# IB_V2_POWER.net
KiCad netlist of a schematic drawn in Altium Designer
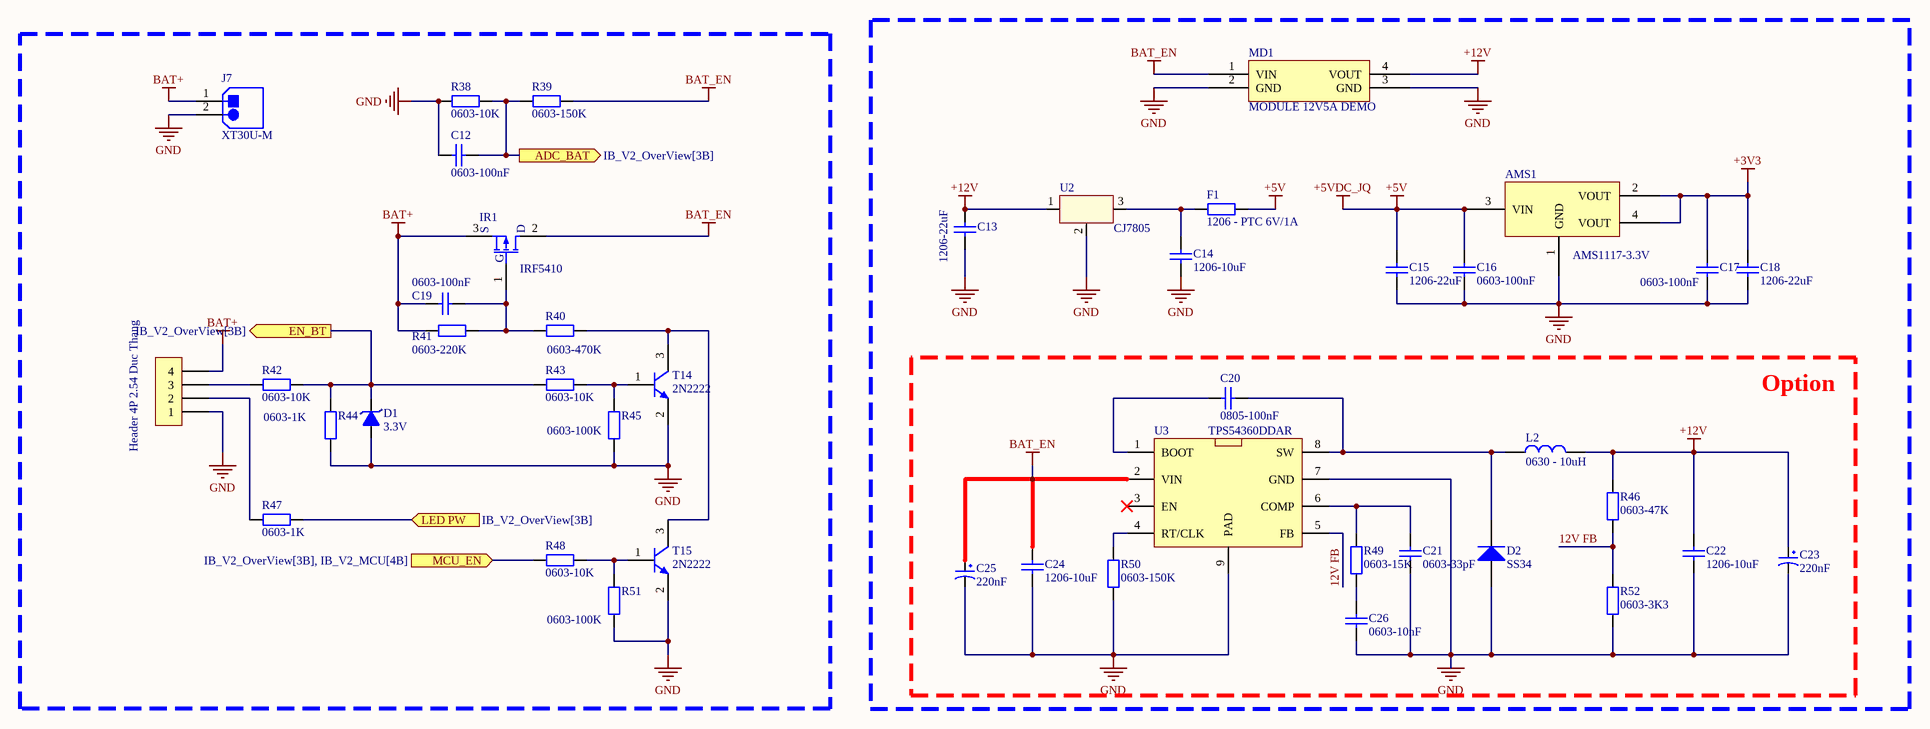
[diagram p0: IB_V2_POWER.SchDoc]

(export (version "E")
  (design (tool "Eeschema 10.0.6"))
  (components
    (comp (ref "AMS1")
      (value "AMS1117-3.3V")
      (footprint "SOT223")
      (description "Dán")
      (libsource (lib "TBS19_MineFiled_V4") (part "AMS1117 SMD"))
    )
    (comp (ref "C12")
      (value "0603-100nF")
      (footprint "Cap 0603")
      (description "50V 100nF X7R ±5% 0603 Multilayer Ceramic Capacitors MLCC - SMD/SMT ROHS")
      (libsource (lib "thuvien_cty") (part "Cap 0603 100nF"))
    )
    (comp (ref "C13")
      (value "1206-22uF")
      (footprint "Cap 1206")
      (description "25V 22uF X5R ±10% 1206 Multilayer Ceramic Capacitors MLCC - SMD/SMT ROHS")
      (libsource (lib "thuvien_cty") (part "Cap 1206 22uF"))
    )
    (comp (ref "C14")
      (value "1206-10uF")
      (footprint "Cap 1206")
      (description "50V 10uF X5R ±10% 1206 Multilayer Ceramic Capacitors MLCC - SMD/SMT ROHS")
      (libsource (lib "thuvien_cty") (part "Cap 1206 10uF"))
    )
    (comp (ref "C15")
      (value "1206-22uF")
      (footprint "Cap 1206")
      (description "25V 22uF X5R ±10% 1206 Multilayer Ceramic Capacitors MLCC - SMD/SMT ROHS")
      (libsource (lib "thuvien_cty") (part "Cap 1206 22uF"))
    )
    (comp (ref "C16")
      (value "0603-100nF")
      (footprint "Cap 0603")
      (description "50V 100nF X7R ±5% 0603 Multilayer Ceramic Capacitors MLCC - SMD/SMT ROHS")
      (libsource (lib "thuvien_cty") (part "Cap 0603 100nF"))
    )
    (comp (ref "C17")
      (value "0603-100nF")
      (footprint "Cap 0603")
      (description "50V 100nF X7R ±5% 0603 Multilayer Ceramic Capacitors MLCC - SMD/SMT ROHS")
      (libsource (lib "thuvien_cty") (part "Cap 0603 100nF"))
    )
    (comp (ref "C18")
      (value "1206-22uF")
      (footprint "Cap 1206")
      (description "25V 22uF X5R ±10% 1206 Multilayer Ceramic Capacitors MLCC - SMD/SMT ROHS")
      (libsource (lib "thuvien_cty") (part "Cap 1206 22uF"))
    )
    (comp (ref "C19")
      (value "0603-100nF")
      (footprint "Cap 0603")
      (description "50V 100nF X7R ±5% 0603 Multilayer Ceramic Capacitors MLCC - SMD/SMT ROHS")
      (libsource (lib "thuvien_cty") (part "Cap 0603 100nF"))
    )
    (comp (ref "C20")
      (value "0805-100nF")
      (footprint "Cap 0805")
      (description "50V 100nF X7R ±10% 0805 Multilayer Ceramic Capacitors MLCC - SMD/SMT ROHS")
      (libsource (lib "thuvien_cty") (part "Cap 0805 100nF"))
    )
    (comp (ref "C21")
      (value "0603-33pF")
      (footprint "Cap 0603")
      (description "50V 33pF C0G ±5% 0603 Multilayer Ceramic Capacitors MLCC - SMD/SMT ROHS")
      (libsource (lib "thuvien_cty") (part "Cap 0603 33pF"))
    )
    (comp (ref "C22")
      (value "1206-10uF")
      (footprint "Cap 1206")
      (description "50V 10uF X5R ±10% 1206 Multilayer Ceramic Capacitors MLCC - SMD/SMT ROHS")
      (libsource (lib "thuvien_cty") (part "Cap 1206 10uF"))
    )
    (comp (ref "C23")
      (value "220nF")
      (footprint "tu hoa 8mm")
      (description "Cắm")
      (libsource (lib "Altium_Lib_by_KhueNguyenCreator") (part "Tu Hoa 220uF 35V 8x12"))
    )
    (comp (ref "C24")
      (value "1206-10uF")
      (footprint "Cap 1206")
      (description "50V 10uF X5R ±10% 1206 Multilayer Ceramic Capacitors MLCC - SMD/SMT ROHS")
      (libsource (lib "thuvien_cty") (part "Cap 1206 10uF"))
    )
    (comp (ref "C25")
      (value "220nF")
      (footprint "tu hoa 8mm")
      (description "Cắm")
      (libsource (lib "Altium_Lib_by_KhueNguyenCreator") (part "Tu Hoa 220uF 35V 8x12"))
    )
    (comp (ref "C26")
      (value "0603-10nF")
      (footprint "Cap 0603")
      (description "50V 10nF X7R ±5% 0603 Multilayer Ceramic Capacitors MLCC - SMD/SMT ROHS")
      (libsource (lib "thuvien_cty") (part "Cap 0603 100nF"))
    )
    (comp (ref "D1")
      (value "3.3V")
      (footprint "DIODE ZENNER SMD SOD80")
      (description "Dán")
      (libsource (lib "TBS19_MineFiled_V4") (part "Diode Zener 3.3V"))
    )
    (comp (ref "D2")
      (value "SS34")
      (footprint "DIODE SMA")
      (description "Dán")
      (libsource (lib "TBS19_MineFiled_V4") (part "Diode SS34 ( 1N5822 )"))
    )
    (comp (ref "F1")
      (value "1206 - PTC 6V/1A")
      (footprint "tro smd 1206")
      (description "Dán")
      (libsource (lib "TBS19_MineFiled_V4") (part "Tro 1206 1% 10R"))
    )
    (comp (ref "H7")
      (value "Header 4P 2.54 Duc Thang")
      (footprint "XH2.54M-4")
      (description "Cắm")
      (libsource (lib "Altium_Lib_by_KhueNguyenCreator") (part "Header 4P 2.54 Duc Thang"))
    )
    (comp (ref "IR1")
      (value "IRF5410")
      (footprint "TO-252")
      (libsource (lib "HTD-AK") (part "Mosfet - DTU40P06"))
    )
    (comp (ref "J7")
      (value "XT30U-M")
      (footprint "XT30U")
      (description "Socket; DC supply; XT30; male; PIN: 2; on PCBs; THT; Colour: yellow")
      (libsource (lib "thuvien_cty") (part "XT30U-M"))
    )
    (comp (ref "L2")
      (value "0630 - 10uH")
      (footprint "0630_Inductor")
      (libsource (lib "TBS19_MineFiled_V4") (part "0630_Inductor"))
    )
    (comp (ref "MD1")
      (value "MODULE 12V5A DEMO")
      (footprint "MODULE 12V5A")
      (libsource (lib "MODULE_12V_5A") (part "MODULE 12V5A DEMO"))
    )
    (comp (ref "R38")
      (value "0603-10K")
      (footprint "RES 0603")
      (description "100mW Thick Film Resistors 75V ±100ppm/℃ ±1% 47kΩ 0603 Chip Resistor - Surface Mount ROHS")
      (libsource (lib "thuvien_cty") (part "Res 0603 47K"))
    )
    (comp (ref "R39")
      (value "0603-150K")
      (footprint "RES 0603")
      (description "100mW Thick Film Resistors 75V ±100ppm/℃ ±1% 820kΩ 0603 Chip Resistor - Surface Mount ROHS")
      (libsource (lib "thuvien_cty") (part "Res 0603 820K"))
    )
    (comp (ref "R40")
      (value "0603-470K")
      (footprint "RES 0603")
      (description "100mW Thick Film Resistors 75V ±100ppm/℃ ±1% 470kΩ 0603 Chip Resistor - Surface Mount ROHS")
      (libsource (lib "thuvien_cty") (part "Res 0603 470K"))
    )
    (comp (ref "R41")
      (value "0603-220K")
      (footprint "RES 0603")
      (description "100mW Thick Film Resistors 75V ±100ppm/℃ ±1% 220kΩ 0603 Chip Resistor - Surface Mount ROHS")
      (libsource (lib "thuvien_cty") (part "Res 0603 220K"))
    )
    (comp (ref "R42")
      (value "0603-10K")
      (footprint "RES 0603")
      (description "0.1W Thick Film Resistors 75V ±100ppm/℃ ±1% 10kΩ 0603 Chip Resistor - Surface Mount ROHS")
      (libsource (lib "thuvien_cty") (part "Res 0603 10K"))
    )
    (comp (ref "R43")
      (value "0603-10K")
      (footprint "RES 0603")
      (description "0.1W Thick Film Resistors 75V ±100ppm/℃ ±1% 10kΩ 0603 Chip Resistor - Surface Mount ROHS")
      (libsource (lib "thuvien_cty") (part "Res 0603 10K"))
    )
    (comp (ref "R44")
      (value "0603-1K")
      (footprint "RES 0603")
      (description "0.1W Thick Film Resistors 75V ±100ppm/℃ ±1% 1kΩ 0603 Chip Resistor - Surface Mount ROHS")
      (libsource (lib "thuvien_cty") (part "Res 0603 1K"))
    )
    (comp (ref "R45")
      (value "0603-100K")
      (footprint "RES 0603")
      (description "100mW Thick Film Resistors 75V ±100ppm/℃ ±1% 100kΩ 0603 Chip Resistor - Surface Mount ROHS")
      (libsource (lib "thuvien_cty") (part "Res 0603 100K"))
    )
    (comp (ref "R46")
      (value "0603-47K")
      (footprint "RES 0603")
      (description "100mW Thick Film Resistors 75V ±100ppm/℃ ±1% 47kΩ 0603 Chip Resistor - Surface Mount ROHS")
      (libsource (lib "thuvien_cty") (part "Res 0603 47K"))
    )
    (comp (ref "R47")
      (value "0603-1K")
      (footprint "RES 0603")
      (description "0.1W Thick Film Resistors 75V ±100ppm/℃ ±1% 1kΩ 0603 Chip Resistor - Surface Mount ROHS")
      (libsource (lib "thuvien_cty") (part "Res 0603 1K"))
    )
    (comp (ref "R48")
      (value "0603-10K")
      (footprint "RES 0603")
      (description "0.1W Thick Film Resistors 75V ±100ppm/℃ ±1% 10kΩ 0603 Chip Resistor - Surface Mount ROHS")
      (libsource (lib "thuvien_cty") (part "Res 0603 10K"))
    )
    (comp (ref "R49")
      (value "0603-15K")
      (footprint "RES 0603")
      (description "100mW Thick Film Resistors 75V ±100ppm/℃ ±1% 15kΩ 0603 Chip Resistor - Surface Mount ROHS")
      (libsource (lib "thuvien_cty") (part "Res 0603 15K"))
    )
    (comp (ref "R50")
      (value "0603-150K")
      (footprint "RES 0603")
      (description "100mW Thick Film Resistors 75V ±100ppm/℃ ±1% 150kΩ 0603 Chip Resistor - Surface Mount ROHS")
      (libsource (lib "thuvien_cty") (part "Res 0603 150K"))
    )
    (comp (ref "R51")
      (value "0603-100K")
      (footprint "RES 0603")
      (description "100mW Thick Film Resistors 75V ±100ppm/℃ ±1% 100kΩ 0603 Chip Resistor - Surface Mount ROHS")
      (libsource (lib "thuvien_cty") (part "Res 0603 100K"))
    )
    (comp (ref "R52")
      (value "0603-3K3")
      (footprint "RES 0603")
      (description "100mW Thick Film Resistors 75V ±100ppm/℃ ±1% 3.3kΩ 0603 Chip Resistor - Surface Mount ROHS")
      (libsource (lib "thuvien_cty") (part "Res 0603 3K3"))
    )
    (comp (ref "T14")
      (value "2N2222")
      (footprint "SOT - 23")
      (libsource (lib "HTD-AK") (part "Transistor - 2N2222"))
    )
    (comp (ref "T15")
      (value "2N2222")
      (footprint "SOT - 23")
      (libsource (lib "HTD-AK") (part "Transistor - 2N2222"))
    )
    (comp (ref "U2") (value "CJ7805") (footprint "To263 2L") (libsource (lib "TG21_SCHLib") (part "7805")))
    (comp (ref "U3")
      (value "TPS54360DDAR")
      (footprint "SOIC-8-EP")
      (description "Step-down type 800mV~58.8V 3.5A 4.5V~60V SOIC-8-EP DC-DC Converters ROHS")
      (libsource (lib "thuvien_cty") (part "TPS54360DDAR"))
    )
  )
  (nets
    (net (code "1") (name "+3V3") (class "Default")
      (node (ref "AMS1") (pin "2") (pinfunction "VOUT_2") (pintype "passive"))
      (node (ref "AMS1") (pin "4") (pinfunction "VOUT_4") (pintype "passive"))
      (node (ref "C17") (pin "1") (pinfunction "1_1") (pintype "passive"))
      (node (ref "C18") (pin "1") (pinfunction "1_1") (pintype "passive"))
    )
    (net (code "2") (name "+5V") (class "Default")
      (node (ref "AMS1") (pin "3") (pinfunction "VIN_3") (pintype "passive"))
      (node (ref "C15") (pin "1") (pinfunction "1_1") (pintype "passive"))
      (node (ref "C16") (pin "1") (pinfunction "1_1") (pintype "passive"))
      (node (ref "F1") (pin "2") (pinfunction "2_2") (pintype "passive"))
    )
    (net (code "3") (name "+12V") (class "Default")
      (node (ref "C13") (pin "1") (pinfunction "1_1") (pintype "passive"))
      (node (ref "C22") (pin "1") (pinfunction "1_1") (pintype "passive"))
      (node (ref "C23") (pin "1") (pinfunction "1_1") (pintype "passive"))
      (node (ref "L2") (pin "2") (pinfunction "2_2") (pintype "passive"))
      (node (ref "MD1") (pin "4") (pinfunction "VOUT_4") (pintype "passive"))
      (node (ref "R46") (pin "2") (pinfunction "2_2") (pintype "passive"))
      (node (ref "U2") (pin "1") (pinfunction "Vin_1") (pintype "passive"))
    )
    (net (code "4") (name "/12V FB") (class "Default")
      (node (ref "R46") (pin "1") (pinfunction "1_1") (pintype "passive"))
      (node (ref "R52") (pin "2") (pinfunction "2_2") (pintype "passive"))
      (node (ref "U3") (pin "5") (pinfunction "FB_5") (pintype "power_in"))
    )
    (net (code "5") (name "/ADC_BAT") (class "Default")
      (node (ref "C12") (pin "2") (pinfunction "2_2") (pintype "passive"))
      (node (ref "R38") (pin "1") (pinfunction "1_1") (pintype "passive"))
      (node (ref "R39") (pin "2") (pinfunction "2_2") (pintype "passive"))
    )
    (net (code "6") (name "/EN_BT") (class "Default")
      (node (ref "D1") (pin "2") (pinfunction "K_2") (pintype "passive"))
      (node (ref "R42") (pin "2") (pinfunction "2_2") (pintype "passive"))
      (node (ref "R43") (pin "1") (pinfunction "1_1") (pintype "passive"))
      (node (ref "R44") (pin "2") (pinfunction "2_2") (pintype "passive"))
    )
    (net (code "7") (name "/LED PW") (class "Default")
      (node (ref "R47") (pin "2") (pinfunction "2_2") (pintype "passive"))
    )
    (net (code "8") (name "/MCU_EN") (class "Default")
      (node (ref "R48") (pin "1") (pinfunction "1_1") (pintype "passive"))
    )
    (net (code "9") (name "BAT+") (class "Default")
      (node (ref "C19") (pin "1") (pinfunction "1_1") (pintype "passive"))
      (node (ref "H7") (pin "4") (pinfunction "4_4") (pintype "passive"))
      (node (ref "IR1") (pin "3") (pinfunction "S_3") (pintype "passive"))
      (node (ref "J7") (pin "1") (pinfunction "1_1") (pintype "power_in"))
      (node (ref "R41") (pin "1") (pinfunction "1_1") (pintype "passive"))
    )
    (net (code "10") (name "BAT_EN") (class "Default")
      (node (ref "C24") (pin "1") (pinfunction "1_1") (pintype "passive"))
      (node (ref "C25") (pin "1") (pinfunction "1_1") (pintype "passive"))
      (node (ref "IR1") (pin "2") (pinfunction "D_2") (pintype "passive"))
      (node (ref "MD1") (pin "1") (pinfunction "VIN_1") (pintype "passive"))
      (node (ref "R39") (pin "1") (pinfunction "1_1") (pintype "passive"))
      (node (ref "U3") (pin "2") (pinfunction "VIN_2") (pintype "power_in"))
    )
    (net (code "11") (name "GND") (class "Default")
      (node (ref "AMS1") (pin "1") (pinfunction "GND_1") (pintype "passive"))
      (node (ref "C12") (pin "1") (pinfunction "1_1") (pintype "passive"))
      (node (ref "C13") (pin "2") (pinfunction "2_2") (pintype "passive"))
      (node (ref "C14") (pin "2") (pinfunction "2_2") (pintype "passive"))
      (node (ref "C15") (pin "2") (pinfunction "2_2") (pintype "passive"))
      (node (ref "C16") (pin "2") (pinfunction "2_2") (pintype "passive"))
      (node (ref "C17") (pin "2") (pinfunction "2_2") (pintype "passive"))
      (node (ref "C18") (pin "2") (pinfunction "2_2") (pintype "passive"))
      (node (ref "C21") (pin "2") (pinfunction "2_2") (pintype "passive"))
      (node (ref "C22") (pin "2") (pinfunction "2_2") (pintype "passive"))
      (node (ref "C23") (pin "2") (pinfunction "2_2") (pintype "passive"))
      (node (ref "C24") (pin "2") (pinfunction "2_2") (pintype "passive"))
      (node (ref "C25") (pin "2") (pinfunction "2_2") (pintype "passive"))
      (node (ref "C26") (pin "2") (pinfunction "2_2") (pintype "passive"))
      (node (ref "D1") (pin "1") (pinfunction "A_1") (pintype "passive"))
      (node (ref "D2") (pin "1") (pinfunction "A_1") (pintype "passive"))
      (node (ref "H7") (pin "1") (pinfunction "1_1") (pintype "passive"))
      (node (ref "J7") (pin "2") (pinfunction "2_2") (pintype "power_in"))
      (node (ref "MD1") (pin "2") (pinfunction "GND_2") (pintype "passive"))
      (node (ref "MD1") (pin "3") (pinfunction "GND_3") (pintype "passive"))
      (node (ref "R38") (pin "2") (pinfunction "2_2") (pintype "passive"))
      (node (ref "R44") (pin "1") (pinfunction "1_1") (pintype "passive"))
      (node (ref "R45") (pin "1") (pinfunction "1_1") (pintype "passive"))
      (node (ref "R50") (pin "1") (pinfunction "1_1") (pintype "passive"))
      (node (ref "R51") (pin "1") (pinfunction "1_1") (pintype "passive"))
      (node (ref "R52") (pin "1") (pinfunction "1_1") (pintype "passive"))
      (node (ref "T14") (pin "2") (pinfunction "E_2") (pintype "passive"))
      (node (ref "T15") (pin "2") (pinfunction "E_2") (pintype "passive"))
      (node (ref "U2") (pin "2") (pinfunction "GND_2") (pintype "passive"))
      (node (ref "U3") (pin "7") (pinfunction "GND_7") (pintype "power_in"))
      (node (ref "U3") (pin "9") (pinfunction "PAD_9") (pintype "power_in"))
    )
    (net (code "12") (name "Net-(C26-Pad1)") (class "Default")
      (node (ref "C26") (pin "1") (pinfunction "1_1") (pintype "passive"))
      (node (ref "R49") (pin "1") (pinfunction "1_1") (pintype "passive"))
    )
    (net (code "13") (name "Net-(D2-K)") (class "Default")
      (node (ref "C20") (pin "1") (pinfunction "1_1") (pintype "passive"))
      (node (ref "D2") (pin "2") (pinfunction "K_2") (pintype "passive"))
      (node (ref "L2") (pin "1") (pinfunction "1_1") (pintype "passive"))
      (node (ref "U3") (pin "8") (pinfunction "SW_8") (pintype "power_in"))
    )
    (net (code "14") (name "Net-(H7-Pad2)") (class "Default")
      (node (ref "H7") (pin "2") (pinfunction "2_2") (pintype "passive"))
      (node (ref "R47") (pin "1") (pinfunction "1_1") (pintype "passive"))
    )
    (net (code "15") (name "Net-(H7-Pad3)") (class "Default")
      (node (ref "H7") (pin "3") (pinfunction "3_3") (pintype "passive"))
      (node (ref "R42") (pin "1") (pinfunction "1_1") (pintype "passive"))
    )
    (net (code "16") (name "Net-(IR1-G)") (class "Default")
      (node (ref "C19") (pin "2") (pinfunction "2_2") (pintype "passive"))
      (node (ref "IR1") (pin "1") (pinfunction "G_1") (pintype "passive"))
      (node (ref "R40") (pin "1") (pinfunction "1_1") (pintype "passive"))
      (node (ref "R41") (pin "2") (pinfunction "2_2") (pintype "passive"))
    )
    (net (code "17") (name "Net-(T14-B)") (class "Default")
      (node (ref "R43") (pin "2") (pinfunction "2_2") (pintype "passive"))
      (node (ref "R45") (pin "2") (pinfunction "2_2") (pintype "passive"))
      (node (ref "T14") (pin "1") (pinfunction "B_1") (pintype "passive"))
    )
    (net (code "18") (name "Net-(T14-C)") (class "Default")
      (node (ref "R40") (pin "2") (pinfunction "2_2") (pintype "passive"))
      (node (ref "T14") (pin "3") (pinfunction "C_3") (pintype "passive"))
      (node (ref "T15") (pin "3") (pinfunction "C_3") (pintype "passive"))
    )
    (net (code "19") (name "Net-(T15-B)") (class "Default")
      (node (ref "R48") (pin "2") (pinfunction "2_2") (pintype "passive"))
      (node (ref "R51") (pin "2") (pinfunction "2_2") (pintype "passive"))
      (node (ref "T15") (pin "1") (pinfunction "B_1") (pintype "passive"))
    )
    (net (code "20") (name "Net-(U2-Vout)") (class "Default")
      (node (ref "C14") (pin "1") (pinfunction "1_1") (pintype "passive"))
      (node (ref "F1") (pin "1") (pinfunction "1_1") (pintype "passive"))
      (node (ref "U2") (pin "3") (pinfunction "Vout_3") (pintype "passive"))
    )
    (net (code "21") (name "Net-(U3-BOOT)") (class "Default")
      (node (ref "C20") (pin "2") (pinfunction "2_2") (pintype "passive"))
      (node (ref "U3") (pin "1") (pinfunction "BOOT_1") (pintype "power_in"))
    )
    (net (code "22") (name "Net-(U3-COMP)") (class "Default")
      (node (ref "C21") (pin "1") (pinfunction "1_1") (pintype "passive"))
      (node (ref "R49") (pin "2") (pinfunction "2_2") (pintype "passive"))
      (node (ref "U3") (pin "6") (pinfunction "COMP_6") (pintype "power_in"))
    )
    (net (code "23") (name "Net-(U3-RT{slash}CLK)") (class "Default")
      (node (ref "R50") (pin "2") (pinfunction "2_2") (pintype "passive"))
      (node (ref "U3") (pin "4") (pinfunction "RT/CLK_4") (pintype "power_in"))
    )
    (net (code "24") (name "unconnected-(U3-EN-Pad3)") (class "Default")
      (node (ref "U3") (pin "3") (pinfunction "EN_3") (pintype "power_in+no_connect"))
    )
  )
)
